# Connectors_LEDs.net
KiCad netlist of a schematic drawn in Altium Designer
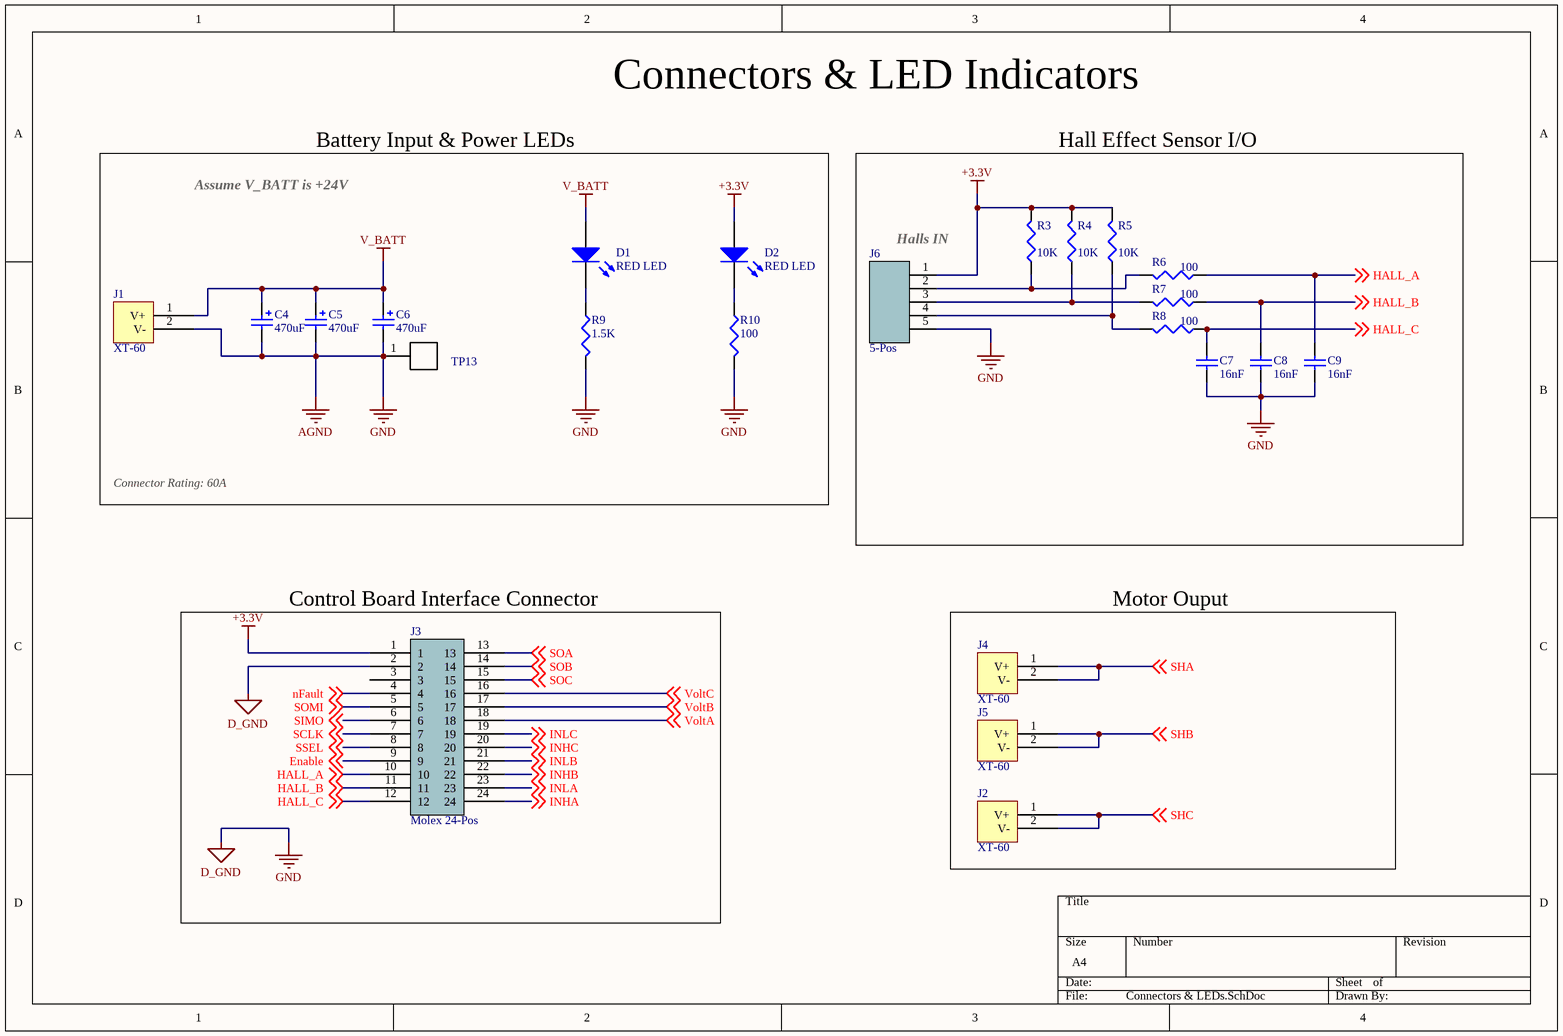
[diagram p0: Connectors & LEDs.SchDoc]

(export (version "E")
  (design (tool "Eeschema 10.0.6"))
  (components
    (comp (ref "C4")
      (value "470uF")
      (footprint "ECA1JHG471")
      (description "Cap Aluminum Lytic 470uF 63V 20% (12.5 X 20mm) Radial 5mm 640mA 2000h 105C Bulk")
      (fields
        (field (name "MANUFACTURER") "Panasonic")
        (field (name "MANUFACTURER PART NUMBER") "ECA-1JHG471")
      )
      (libsource (lib "ECAR_LIBARY") (part "ECA-1JHG471"))
    )
    (comp (ref "C5")
      (value "470uF")
      (footprint "ECA1JHG471")
      (description "Cap Aluminum Lytic 470uF 63V 20% (12.5 X 20mm) Radial 5mm 640mA 2000h 105C Bulk")
      (fields
        (field (name "MANUFACTURER") "Panasonic")
        (field (name "MANUFACTURER PART NUMBER") "ECA-1JHG471")
      )
      (libsource (lib "ECAR_LIBARY") (part "ECA-1JHG471"))
    )
    (comp (ref "C6")
      (value "470uF")
      (footprint "ECA1JHG471")
      (description "Cap Aluminum Lytic 470uF 63V 20% (12.5 X 20mm) Radial 5mm 640mA 2000h 105C Bulk")
      (fields
        (field (name "MANUFACTURER") "Panasonic")
        (field (name "MANUFACTURER PART NUMBER") "ECA-1JHG471")
      )
      (libsource (lib "ECAR_LIBARY") (part "ECA-1JHG471"))
    )
    (comp (ref "C7")
      (value "16nF")
      (footprint "0603 CAP Medium")
      (description "Multilayer Ceramic Capacitors MLCC - SMD/SMT 50volts 0.016uF 10% X7R")
      (fields
        (field (name "MANUFACTURER") "Kyocera AVX")
        (field (name "MANUFACTURER PART NUMBER") "06035C163KAT2A")
      )
      (libsource (lib "ECAR_LIBARY") (part "06035C163KAT2A"))
    )
    (comp (ref "C8")
      (value "16nF")
      (footprint "0603 CAP Medium")
      (description "Multilayer Ceramic Capacitors MLCC - SMD/SMT 50volts 0.016uF 10% X7R")
      (fields
        (field (name "MANUFACTURER") "Kyocera AVX")
        (field (name "MANUFACTURER PART NUMBER") "06035C163KAT2A")
      )
      (libsource (lib "ECAR_LIBARY") (part "06035C163KAT2A"))
    )
    (comp (ref "C9")
      (value "16nF")
      (footprint "0603 CAP Medium")
      (description "Multilayer Ceramic Capacitors MLCC - SMD/SMT 50volts 0.016uF 10% X7R")
      (fields
        (field (name "MANUFACTURER") "Kyocera AVX")
        (field (name "MANUFACTURER PART NUMBER") "06035C163KAT2A")
      )
      (libsource (lib "ECAR_LIBARY") (part "06035C163KAT2A"))
    )
    (comp (ref "D1")
      (value "RED LED")
      (footprint "CAPC1608X05L - Polarized")
      (description "LED RED CLEAR 0603 SMD")
      (fields
        (field (name "MANUFACTURER") "Vishay Lite-On")
        (field (name "MANUFACTURER PART NUMBER") "LTST-C191KRKT")
      )
      (libsource (lib "ECar Reference LIbary") (part "LTST-C191KRKT"))
    )
    (comp (ref "D2")
      (value "RED LED")
      (footprint "CAPC1608X05L - Polarized")
      (description "LED RED CLEAR 0603 SMD")
      (fields
        (field (name "MANUFACTURER") "Vishay Lite-On")
        (field (name "MANUFACTURER PART NUMBER") "LTST-C191KRKT")
      )
      (libsource (lib "ECar Reference LIbary") (part "LTST-C191KRKT"))
    )
    (comp (ref "J1")
      (value "XT-60")
      (footprint "XTC60PW-M")
      (description "XT-60 Power Connector")
      (libsource (lib "ECAR_LIBARY") (part "XT-60"))
    )
    (comp (ref "J2")
      (value "XT-60")
      (footprint "XTC60PW-M")
      (description "XT-60 Power Connector")
      (libsource (lib "ECAR_LIBARY") (part "XT-60"))
    )
    (comp (ref "J3")
      (value "Molex 24-Pos")
      (footprint "PCBComponent_1")
      (libsource (lib "MOSFET Board Schematic Library") (part "Molex 24-Pos (0039301240)"))
    )
    (comp (ref "J4")
      (value "XT-60")
      (footprint "XTC60PW-M")
      (description "XT-60 Power Connector")
      (libsource (lib "ECAR_LIBARY") (part "XT-60"))
    )
    (comp (ref "J5")
      (value "XT-60")
      (footprint "XTC60PW-M")
      (description "XT-60 Power Connector")
      (libsource (lib "ECAR_LIBARY") (part "XT-60"))
    )
    (comp (ref "J6")
      (value "5-Pos")
      (footprint "Hirose 5-pos")
      (libsource (lib "MOSFET Board Schematic Library") (part "5 pos"))
    )
    (comp (ref "R3")
      (value "10K")
      (footprint "RES 0603 MEDIUM")
      (description "Resistor")
      (fields (field (name "Comment") "Res3") (field (name "PUBLISHER") "Altium Limited"))
      (libsource (lib "Miscellaneous Devices") (part "Res3"))
    )
    (comp (ref "R4")
      (value "10K")
      (footprint "RES 0603 MEDIUM")
      (description "Resistor")
      (fields (field (name "Comment") "Res3") (field (name "PUBLISHER") "Altium Limited"))
      (libsource (lib "Miscellaneous Devices") (part "Res3"))
    )
    (comp (ref "R5")
      (value "10K")
      (footprint "RES 0603 MEDIUM")
      (description "Resistor")
      (fields (field (name "Comment") "Res3") (field (name "PUBLISHER") "Altium Limited"))
      (libsource (lib "Miscellaneous Devices") (part "Res3"))
    )
    (comp (ref "R6")
      (value "100")
      (footprint "RES 0603 MEDIUM")
      (description "Resistor")
      (fields (field (name "Comment") "Res3") (field (name "PUBLISHER") "Altium Limited"))
      (libsource (lib "Miscellaneous Devices") (part "Res3"))
    )
    (comp (ref "R7")
      (value "100")
      (footprint "RES 0603 MEDIUM")
      (description "Resistor")
      (fields (field (name "Comment") "Res3") (field (name "PUBLISHER") "Altium Limited"))
      (libsource (lib "Miscellaneous Devices") (part "Res3"))
    )
    (comp (ref "R8")
      (value "100")
      (footprint "RES 0603 MEDIUM")
      (description "Resistor")
      (fields (field (name "Comment") "Res3") (field (name "PUBLISHER") "Altium Limited"))
      (libsource (lib "Miscellaneous Devices") (part "Res3"))
    )
    (comp (ref "R9")
      (value "1.5K")
      (footprint "0805 Res")
      (description "Resistor")
      (fields (field (name "Comment") "Res3") (field (name "PUBLISHER") "Altium Limited"))
      (libsource (lib "Miscellaneous Devices") (part "Res3"))
    )
    (comp (ref "R10")
      (value "100")
      (footprint "RES 0603 MEDIUM")
      (description "Resistor")
      (fields (field (name "Comment") "Res3") (field (name "PUBLISHER") "Altium Limited"))
      (libsource (lib "Miscellaneous Devices") (part "Res3"))
    )
    (comp (ref "TP13")
      (value "1625854-3")
      (footprint "TE_RCU-0C")
      (description "0603 PROBE PAD")
      (fields (field (name "MF") "TE Connectivity") (field (name "DIGI-KEY_PART_NUMBER") "A106145CT-ND"))
      (libsource (lib "ECar Reference LIbary") (part "RCU-0C"))
    )
  )
  (nets
    (net (code "1") (name "+3.3V") (class "Default")
      (node (ref "D2") (pin "1") (pinfunction "A_1") (pintype "passive"))
      (node (ref "J3") (pin "1") (pinfunction "1_1") (pintype "passive"))
      (node (ref "J6") (pin "1") (pinfunction "1_1") (pintype "passive"))
      (node (ref "R3") (pin "2") (pinfunction "2_2") (pintype "passive"))
      (node (ref "R4") (pin "2") (pinfunction "2_2") (pintype "passive"))
      (node (ref "R5") (pin "2") (pinfunction "2_2") (pintype "passive"))
    )
    (net (code "2") (name "AGND") (class "Default")
      (node (ref "C4") (pin "2") (pinfunction "2_2") (pintype "passive"))
      (node (ref "C5") (pin "2") (pinfunction "2_2") (pintype "passive"))
      (node (ref "C6") (pin "2") (pinfunction "2_2") (pintype "passive"))
      (node (ref "C7") (pin "1") (pinfunction "1_1") (pintype "passive"))
      (node (ref "C8") (pin "1") (pinfunction "1_1") (pintype "passive"))
      (node (ref "C9") (pin "1") (pinfunction "1_1") (pintype "passive"))
      (node (ref "J1") (pin "2") (pinfunction "V-_2") (pintype "power_in"))
      (node (ref "J3") (pin "2") (pinfunction "2_2") (pintype "passive"))
      (node (ref "J6") (pin "5") (pinfunction "5_5") (pintype "passive"))
      (node (ref "R10") (pin "2") (pinfunction "2_2") (pintype "passive"))
      (node (ref "R9") (pin "2") (pinfunction "2_2") (pintype "passive"))
      (node (ref "TP13") (pin "1") (pinfunction "1_1") (pintype "passive"))
    )
    (net (code "3") (name "Enable") (class "Default")
      (node (ref "J3") (pin "9") (pinfunction "9_9") (pintype "passive"))
    )
    (net (code "4") (name "HALL_A") (class "Default")
      (node (ref "C9") (pin "2") (pinfunction "2_2") (pintype "passive"))
      (node (ref "J3") (pin "10") (pinfunction "10_10") (pintype "passive"))
      (node (ref "R6") (pin "1") (pinfunction "1_1") (pintype "passive"))
    )
    (net (code "5") (name "HALL_B") (class "Default")
      (node (ref "C8") (pin "2") (pinfunction "2_2") (pintype "passive"))
      (node (ref "J3") (pin "11") (pinfunction "11_11") (pintype "passive"))
      (node (ref "R7") (pin "1") (pinfunction "1_1") (pintype "passive"))
    )
    (net (code "6") (name "HALL_C") (class "Default")
      (node (ref "C7") (pin "2") (pinfunction "2_2") (pintype "passive"))
      (node (ref "J3") (pin "12") (pinfunction "12_12") (pintype "passive"))
      (node (ref "R8") (pin "1") (pinfunction "1_1") (pintype "passive"))
    )
    (net (code "7") (name "INHA") (class "Default")
      (node (ref "J3") (pin "24") (pinfunction "24_24") (pintype "passive"))
    )
    (net (code "8") (name "INHB") (class "Default")
      (node (ref "J3") (pin "22") (pinfunction "22_22") (pintype "passive"))
    )
    (net (code "9") (name "INHC") (class "Default")
      (node (ref "J3") (pin "20") (pinfunction "20_20") (pintype "passive"))
    )
    (net (code "10") (name "INLA") (class "Default")
      (node (ref "J3") (pin "23") (pinfunction "23_23") (pintype "passive"))
    )
    (net (code "11") (name "INLB") (class "Default")
      (node (ref "J3") (pin "21") (pinfunction "21_21") (pintype "passive"))
    )
    (net (code "12") (name "INLC") (class "Default")
      (node (ref "J3") (pin "19") (pinfunction "19_19") (pintype "passive"))
    )
    (net (code "13") (name "Net-(D1-K)") (class "Default")
      (node (ref "D1") (pin "2") (pinfunction "K_2") (pintype "passive"))
      (node (ref "R9") (pin "1") (pinfunction "1_1") (pintype "passive"))
    )
    (net (code "14") (name "Net-(D2-K)") (class "Default")
      (node (ref "D2") (pin "2") (pinfunction "K_2") (pintype "passive"))
      (node (ref "R10") (pin "1") (pinfunction "1_1") (pintype "passive"))
    )
    (net (code "15") (name "Net-(J6-Pad2)") (class "Default")
      (node (ref "J6") (pin "2") (pinfunction "2_2") (pintype "passive"))
      (node (ref "R3") (pin "1") (pinfunction "1_1") (pintype "passive"))
      (node (ref "R6") (pin "2") (pinfunction "2_2") (pintype "passive"))
    )
    (net (code "16") (name "Net-(J6-Pad3)") (class "Default")
      (node (ref "J6") (pin "3") (pinfunction "3_3") (pintype "passive"))
      (node (ref "R4") (pin "1") (pinfunction "1_1") (pintype "passive"))
      (node (ref "R7") (pin "2") (pinfunction "2_2") (pintype "passive"))
    )
    (net (code "17") (name "Net-(J6-Pad4)") (class "Default")
      (node (ref "J6") (pin "4") (pinfunction "4_4") (pintype "passive"))
      (node (ref "R5") (pin "1") (pinfunction "1_1") (pintype "passive"))
      (node (ref "R8") (pin "2") (pinfunction "2_2") (pintype "passive"))
    )
    (net (code "18") (name "SCLK") (class "Default")
      (node (ref "J3") (pin "7") (pinfunction "7_7") (pintype "passive"))
    )
    (net (code "19") (name "SHA") (class "Default")
      (node (ref "J4") (pin "1") (pinfunction "V+_1") (pintype "power_in"))
      (node (ref "J4") (pin "2") (pinfunction "V-_2") (pintype "power_in"))
    )
    (net (code "20") (name "SHB") (class "Default")
      (node (ref "J5") (pin "1") (pinfunction "V+_1") (pintype "power_in"))
      (node (ref "J5") (pin "2") (pinfunction "V-_2") (pintype "power_in"))
    )
    (net (code "21") (name "SHC") (class "Default")
      (node (ref "J2") (pin "1") (pinfunction "V+_1") (pintype "power_in"))
      (node (ref "J2") (pin "2") (pinfunction "V-_2") (pintype "power_in"))
    )
    (net (code "22") (name "SIMO") (class "Default")
      (node (ref "J3") (pin "6") (pinfunction "6_6") (pintype "passive"))
    )
    (net (code "23") (name "SOA") (class "Default")
      (node (ref "J3") (pin "13") (pinfunction "13_13") (pintype "passive"))
    )
    (net (code "24") (name "SOB") (class "Default")
      (node (ref "J3") (pin "14") (pinfunction "14_14") (pintype "passive"))
    )
    (net (code "25") (name "SOC") (class "Default")
      (node (ref "J3") (pin "15") (pinfunction "15_15") (pintype "passive"))
    )
    (net (code "26") (name "SOMI") (class "Default")
      (node (ref "J3") (pin "5") (pinfunction "5_5") (pintype "passive"))
    )
    (net (code "27") (name "SSEL") (class "Default")
      (node (ref "J3") (pin "8") (pinfunction "8_8") (pintype "passive"))
    )
    (net (code "28") (name "V_BATT") (class "Default")
      (node (ref "C4") (pin "1") (pinfunction "1_1") (pintype "passive"))
      (node (ref "C5") (pin "1") (pinfunction "1_1") (pintype "passive"))
      (node (ref "C6") (pin "1") (pinfunction "1_1") (pintype "passive"))
      (node (ref "D1") (pin "1") (pinfunction "A_1") (pintype "passive"))
      (node (ref "J1") (pin "1") (pinfunction "V+_1") (pintype "power_in"))
    )
    (net (code "29") (name "VoltA") (class "Default")
      (node (ref "J3") (pin "18") (pinfunction "18_18") (pintype "passive"))
    )
    (net (code "30") (name "VoltB") (class "Default")
      (node (ref "J3") (pin "17") (pinfunction "17_17") (pintype "passive"))
    )
    (net (code "31") (name "VoltC") (class "Default")
      (node (ref "J3") (pin "16") (pinfunction "16_16") (pintype "passive"))
    )
    (net (code "32") (name "nFault") (class "Default")
      (node (ref "J3") (pin "4") (pinfunction "4_4") (pintype "passive"))
    )
    (net (code "33") (name "unconnected-(J3-Pad3)") (class "Default")
      (node (ref "J3") (pin "3") (pinfunction "3_3") (pintype "passive"))
    )
  )
)
